# Sheet3.net
KiCad netlist of a schematic drawn in Altium Designer
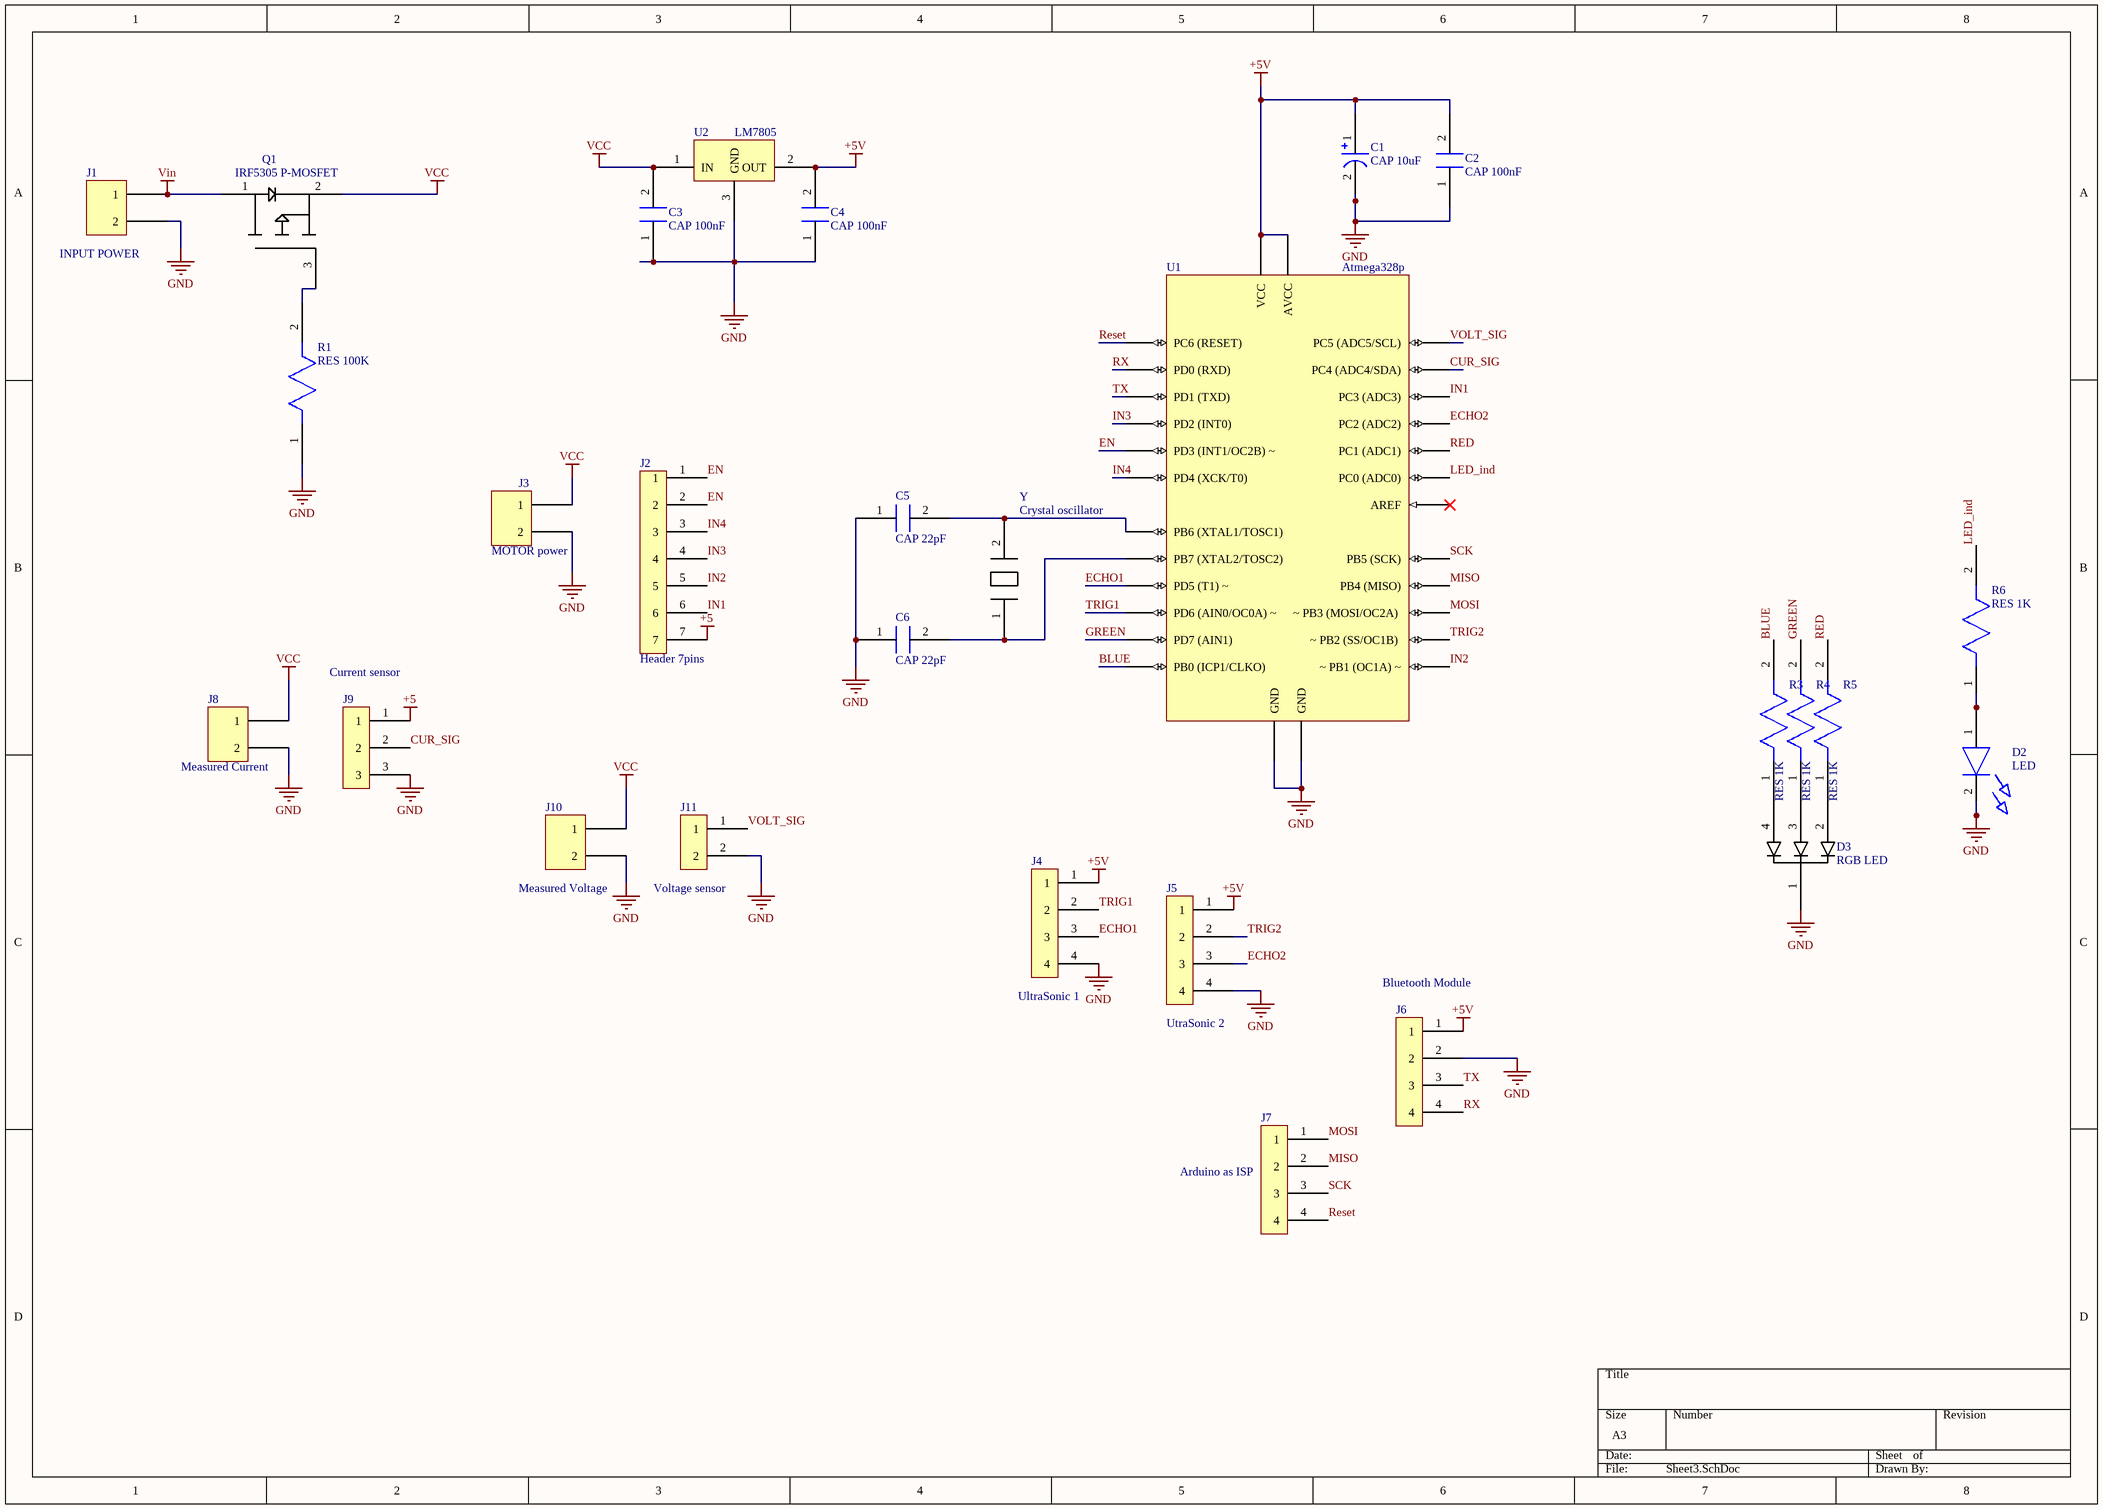
[diagram p0: Sheet3.SchDoc]

(export (version "E")
  (design (tool "Eeschema 10.0.6"))
  (components
    (comp (ref "C1")
      (value "CAP 10uF")
      (footprint "Cap 10uF")
      (libsource (lib "Schlib1") (part "CAP 10uF_1"))
    )
    (comp (ref "C2")
      (value "CAP 100nF")
      (footprint "Cap 100nF")
      (libsource (lib "Schlib1") (part "CAP 100nF"))
    )
    (comp (ref "C3")
      (value "CAP 100nF")
      (footprint "Cap 100nF")
      (libsource (lib "Schlib1") (part "CAP 100nF"))
    )
    (comp (ref "C4")
      (value "CAP 100nF")
      (footprint "Cap 100nF")
      (libsource (lib "Schlib1") (part "CAP 100nF"))
    )
    (comp (ref "C5") (value "CAP 22pF") (footprint "Cap 22pF") (libsource (lib "Schlib1") (part "CAP 22pF")))
    (comp (ref "C6") (value "CAP 22pF") (footprint "Cap 22pF") (libsource (lib "Schlib1") (part "CAP 22pF")))
    (comp (ref "D2") (value "LED") (footprint "LED") (libsource (lib "Schlib1") (part "LED")))
    (comp (ref "D3") (value "RGB LED") (footprint "RGB LED") (libsource (lib "Schlib1") (part "RGB LED")))
    (comp (ref "J1")
      (value "INPUT POWER")
      (footprint "Terminal Block 2pin")
      (libsource (lib "Schlib1") (part "TerminalBlock 2pin"))
    )
    (comp (ref "J2")
      (value "Header 7pins")
      (footprint "Header 7pins")
      (libsource (lib "Schlib1") (part "Header 7pins"))
    )
    (comp (ref "J3")
      (value "MOTOR power")
      (footprint "Terminal Block 2pin")
      (libsource (lib "Schlib1") (part "TerminalBlock 2pin"))
    )
    (comp (ref "J4")
      (value "UltraSonic 1")
      (footprint "Header 4pin")
      (libsource (lib "Schlib1") (part "Headers 4pin"))
    )
    (comp (ref "J5")
      (value "UtraSonic 2")
      (footprint "Header 4pin")
      (libsource (lib "Schlib1") (part "Headers 4pin"))
    )
    (comp (ref "J6")
      (value "Bluetooth Module")
      (footprint "Header 4pin")
      (libsource (lib "Schlib1") (part "Headers 4pin"))
    )
    (comp (ref "J7")
      (value "Arduino as ISP")
      (footprint "Header 4pin")
      (libsource (lib "Schlib1") (part "Headers 4pin"))
    )
    (comp (ref "J8")
      (value "Measured Current")
      (footprint "Terminal Block 2pin")
      (libsource (lib "Schlib1") (part "TerminalBlock 2pin"))
    )
    (comp (ref "J9")
      (value "Current sensor")
      (footprint "Headers 3pins")
      (libsource (lib "Schlib1") (part "Header 3pins"))
    )
    (comp (ref "J10")
      (value "Measured Voltage")
      (footprint "Terminal Block 2pin")
      (libsource (lib "Schlib1") (part "TerminalBlock 2pin"))
    )
    (comp (ref "J11")
      (value "Voltage sensor")
      (footprint "Header 2pins")
      (libsource (lib "Schlib1") (part "Headers 2pins"))
    )
    (comp (ref "Q1")
      (value "IRF5305 P-MOSFET")
      (footprint "IRF5305")
      (libsource (lib "Schlib1") (part "IRF5305 P-MOSFET"))
    )
    (comp (ref "R1") (value "RES 100K") (footprint "Res100K") (libsource (lib "Schlib1") (part "RES 100K")))
    (comp (ref "R3") (value "RES 1K") (footprint "Res 1K") (libsource (lib "Schlib1") (part "RES 1K")))
    (comp (ref "R4") (value "RES 1K") (footprint "Res 1K") (libsource (lib "Schlib1") (part "RES 1K")))
    (comp (ref "R5") (value "RES 1K") (footprint "Res 1K") (libsource (lib "Schlib1") (part "RES 1K")))
    (comp (ref "R6") (value "RES 1K") (footprint "Res 1K") (libsource (lib "Schlib1") (part "RES 1K")))
    (comp (ref "U1")
      (value "Atmega328p")
      (footprint "ATMega 328 P-PU - duplicate")
      (libsource (lib "Schlib1") (part "Atmega328p"))
    )
    (comp (ref "U2") (value "LM7805") (footprint "LM7805") (libsource (lib "Schlib1") (part "LM7805")))
    (comp (ref "Y")
      (value "Crystal oscillator")
      (footprint "Crrystal 16MHZ")
      (libsource (lib "Schlib1") (part "Crystal oscillator"))
    )
  )
  (nets
    (net (code "1") (name "+5") (class "Default")
      (node (ref "J2") (pin "7") (pinfunction "7_7") (pintype "passive"))
      (node (ref "J9") (pin "1") (pinfunction "1_1") (pintype "passive"))
    )
    (net (code "2") (name "+5V") (class "Default")
      (node (ref "C1") (pin "1") (pinfunction "1_1") (pintype "passive"))
      (node (ref "C2") (pin "2") (pinfunction "2_2") (pintype "passive"))
      (node (ref "C4") (pin "2") (pinfunction "2_2") (pintype "passive"))
      (node (ref "J4") (pin "1") (pinfunction "1_1") (pintype "passive"))
      (node (ref "J5") (pin "1") (pinfunction "1_1") (pintype "passive"))
      (node (ref "J6") (pin "1") (pinfunction "1_1") (pintype "passive"))
      (node (ref "U1") (pin "20") (pinfunction "AVCC_20") (pintype "passive"))
      (node (ref "U1") (pin "7") (pinfunction "VCC_7") (pintype "passive"))
      (node (ref "U2") (pin "2") (pinfunction "OUT_2") (pintype "passive"))
    )
    (net (code "4") (name "/BLUE") (class "Default")
      (node (ref "R3") (pin "2") (pinfunction "4_2") (pintype "passive"))
      (node (ref "U1") (pin "14") (pinfunction "PB0_(ICP1/CLKO)_14") (pintype "bidirectional"))
    )
    (net (code "5") (name "/CUR_SIG") (class "Default")
      (node (ref "J9") (pin "2") (pinfunction "2_2") (pintype "passive"))
      (node (ref "U1") (pin "27") (pinfunction "PC4_(ADC4/SDA)_27") (pintype "bidirectional"))
    )
    (net (code "6") (name "/ECHO1") (class "Default")
      (node (ref "J4") (pin "3") (pinfunction "3_3") (pintype "passive"))
      (node (ref "U1") (pin "11") (pinfunction "PD5_(T1)_~_11") (pintype "bidirectional"))
    )
    (net (code "7") (name "/ECHO2") (class "Default")
      (node (ref "J5") (pin "3") (pinfunction "3_3") (pintype "passive"))
      (node (ref "U1") (pin "25") (pinfunction "PC2_(ADC2)_25") (pintype "bidirectional"))
    )
    (net (code "8") (name "/EN") (class "Default")
      (node (ref "J2") (pin "1") (pinfunction "1_1") (pintype "passive"))
      (node (ref "J2") (pin "2") (pinfunction "2_2") (pintype "passive"))
      (node (ref "U1") (pin "5") (pinfunction "PD3_(INT1/OC2B)_~_5") (pintype "bidirectional"))
    )
    (net (code "9") (name "/GREEN") (class "Default")
      (node (ref "R4") (pin "2") (pinfunction "4_2") (pintype "passive"))
      (node (ref "U1") (pin "13") (pinfunction "PD7_(AIN1)_13") (pintype "bidirectional"))
    )
    (net (code "10") (name "/IN1") (class "Default")
      (node (ref "J2") (pin "6") (pinfunction "6_6") (pintype "passive"))
      (node (ref "U1") (pin "26") (pinfunction "PC3_(ADC3)_26") (pintype "bidirectional"))
    )
    (net (code "11") (name "/IN2") (class "Default")
      (node (ref "J2") (pin "5") (pinfunction "5_5") (pintype "passive"))
      (node (ref "U1") (pin "15") (pinfunction "~_PB1_(OC1A)_~_15") (pintype "bidirectional"))
    )
    (net (code "12") (name "/IN3") (class "Default")
      (node (ref "J2") (pin "4") (pinfunction "4_4") (pintype "passive"))
      (node (ref "U1") (pin "4") (pinfunction "PD2_(INT0)_4") (pintype "bidirectional"))
    )
    (net (code "13") (name "/IN4") (class "Default")
      (node (ref "J2") (pin "3") (pinfunction "3_3") (pintype "passive"))
      (node (ref "U1") (pin "6") (pinfunction "PD4_(XCK/T0)_6") (pintype "bidirectional"))
    )
    (net (code "14") (name "/LED_ind") (class "Default")
      (node (ref "R6") (pin "2") (pinfunction "4_2") (pintype "passive"))
      (node (ref "U1") (pin "23") (pinfunction "PC0_(ADC0)_23") (pintype "bidirectional"))
    )
    (net (code "15") (name "/MISO") (class "Default")
      (node (ref "J7") (pin "2") (pinfunction "2_2") (pintype "passive"))
      (node (ref "U1") (pin "18") (pinfunction "PB4_(MISO)_18") (pintype "bidirectional"))
    )
    (net (code "16") (name "/MOSI") (class "Default")
      (node (ref "J7") (pin "1") (pinfunction "1_1") (pintype "passive"))
      (node (ref "U1") (pin "17") (pinfunction "~_PB3_(MOSI/OC2A)_17") (pintype "bidirectional"))
    )
    (net (code "17") (name "/RED") (class "Default")
      (node (ref "R5") (pin "2") (pinfunction "4_2") (pintype "passive"))
      (node (ref "U1") (pin "24") (pinfunction "PC1_(ADC1)_24") (pintype "bidirectional"))
    )
    (net (code "18") (name "/RX") (class "Default")
      (node (ref "J6") (pin "4") (pinfunction "4_4") (pintype "passive"))
      (node (ref "U1") (pin "2") (pinfunction "PD0_(RXD)_2") (pintype "bidirectional"))
    )
    (net (code "19") (name "/Reset") (class "Default")
      (node (ref "J7") (pin "4") (pinfunction "4_4") (pintype "passive"))
      (node (ref "U1") (pin "1") (pinfunction "PC6_(RESET)_1") (pintype "bidirectional"))
    )
    (net (code "20") (name "/SCK") (class "Default")
      (node (ref "J7") (pin "3") (pinfunction "3_3") (pintype "passive"))
      (node (ref "U1") (pin "19") (pinfunction "PB5_(SCK)_19") (pintype "bidirectional"))
    )
    (net (code "21") (name "/TRIG1") (class "Default")
      (node (ref "J4") (pin "2") (pinfunction "2_2") (pintype "passive"))
      (node (ref "U1") (pin "12") (pinfunction "PD6_(AIN0/OC0A)_~_12") (pintype "bidirectional"))
    )
    (net (code "22") (name "/TRIG2") (class "Default")
      (node (ref "J5") (pin "2") (pinfunction "2_2") (pintype "passive"))
      (node (ref "U1") (pin "16") (pinfunction "~_PB2_(SS/OC1B)_16") (pintype "bidirectional"))
    )
    (net (code "23") (name "/TX") (class "Default")
      (node (ref "J6") (pin "3") (pinfunction "3_3") (pintype "passive"))
      (node (ref "U1") (pin "3") (pinfunction "PD1_(TXD)_3") (pintype "bidirectional"))
    )
    (net (code "24") (name "/VOLT_SIG") (class "Default")
      (node (ref "J11") (pin "1") (pinfunction "1_1") (pintype "passive"))
      (node (ref "U1") (pin "28") (pinfunction "PC5_(ADC5/SCL)_28") (pintype "bidirectional"))
    )
    (net (code "25") (name "GND") (class "Default")
      (node (ref "C1") (pin "2") (pinfunction "2_2") (pintype "passive"))
      (node (ref "C2") (pin "1") (pinfunction "1_1") (pintype "passive"))
      (node (ref "C3") (pin "1") (pinfunction "1_1") (pintype "passive"))
      (node (ref "C4") (pin "1") (pinfunction "1_1") (pintype "passive"))
      (node (ref "C5") (pin "1") (pinfunction "1_1") (pintype "passive"))
      (node (ref "C6") (pin "1") (pinfunction "1_1") (pintype "passive"))
      (node (ref "D2") (pin "2") (pinfunction "6_2") (pintype "passive"))
      (node (ref "D3") (pin "1") (pinfunction "(-)_1") (pintype "passive"))
      (node (ref "J1") (pin "2") (pinfunction "2_2") (pintype "passive"))
      (node (ref "J10") (pin "2") (pinfunction "2_2") (pintype "passive"))
      (node (ref "J11") (pin "2") (pinfunction "2_2") (pintype "passive"))
      (node (ref "J3") (pin "2") (pinfunction "2_2") (pintype "passive"))
      (node (ref "J4") (pin "4") (pinfunction "4_4") (pintype "passive"))
      (node (ref "J5") (pin "4") (pinfunction "4_4") (pintype "passive"))
      (node (ref "J6") (pin "2") (pinfunction "2_2") (pintype "passive"))
      (node (ref "J8") (pin "2") (pinfunction "2_2") (pintype "passive"))
      (node (ref "J9") (pin "3") (pinfunction "3_3") (pintype "passive"))
      (node (ref "R1") (pin "1") (pinfunction "3_1") (pintype "passive"))
      (node (ref "U1") (pin "22") (pinfunction "GND_22") (pintype "passive"))
      (node (ref "U1") (pin "8") (pinfunction "GND_8") (pintype "passive"))
      (node (ref "U2") (pin "3") (pinfunction "GND_3") (pintype "power_in"))
    )
    (net (code "26") (name "Net-(D2-7)") (class "Default")
      (node (ref "D2") (pin "1") (pinfunction "7_1") (pintype "passive"))
      (node (ref "R6") (pin "1") (pinfunction "3_1") (pintype "passive"))
    )
    (net (code "27") (name "Net-(D3-B)") (class "Default")
      (node (ref "D3") (pin "4") (pinfunction "B_4") (pintype "passive"))
      (node (ref "R3") (pin "1") (pinfunction "3_1") (pintype "passive"))
    )
    (net (code "28") (name "Net-(D3-G)") (class "Default")
      (node (ref "D3") (pin "3") (pinfunction "G_3") (pintype "passive"))
      (node (ref "R4") (pin "1") (pinfunction "3_1") (pintype "passive"))
    )
    (net (code "29") (name "Net-(D3-R)") (class "Default")
      (node (ref "D3") (pin "2") (pinfunction "R_2") (pintype "passive"))
      (node (ref "R5") (pin "1") (pinfunction "3_1") (pintype "passive"))
    )
    (net (code "30") (name "Net-(Q1-G)") (class "Default")
      (node (ref "Q1") (pin "3") (pinfunction "G_3") (pintype "passive"))
      (node (ref "R1") (pin "2") (pinfunction "4_2") (pintype "passive"))
    )
    (net (code "31") (name "Net-(U1-PB6_(XTAL1{slash}TOSC1))") (class "Default")
      (node (ref "C5") (pin "2") (pinfunction "2_2") (pintype "passive"))
      (node (ref "U1") (pin "9") (pinfunction "PB6_(XTAL1/TOSC1)_9") (pintype "bidirectional"))
      (node (ref "Y") (pin "2") (pinfunction "2_2") (pintype "passive"))
    )
    (net (code "32") (name "Net-(U1-PB7_(XTAL2{slash}TOSC2))") (class "Default")
      (node (ref "C6") (pin "2") (pinfunction "2_2") (pintype "passive"))
      (node (ref "U1") (pin "10") (pinfunction "PB7_(XTAL2/TOSC2)_10") (pintype "bidirectional"))
      (node (ref "Y") (pin "1") (pinfunction "1_1") (pintype "passive"))
    )
    (net (code "33") (name "VCC") (class "Default")
      (node (ref "C3") (pin "2") (pinfunction "2_2") (pintype "passive"))
      (node (ref "J10") (pin "1") (pinfunction "1_1") (pintype "passive"))
      (node (ref "J3") (pin "1") (pinfunction "1_1") (pintype "passive"))
      (node (ref "J8") (pin "1") (pinfunction "1_1") (pintype "passive"))
      (node (ref "Q1") (pin "2") (pinfunction "S_2") (pintype "passive"))
      (node (ref "U2") (pin "1") (pinfunction "IN_1") (pintype "passive"))
    )
    (net (code "34") (name "Vin") (class "Default")
      (node (ref "J1") (pin "1") (pinfunction "1_1") (pintype "passive"))
      (node (ref "Q1") (pin "1") (pinfunction "D_1") (pintype "passive"))
    )
    (net (code "35") (name "unconnected-(U1-AREF-Pad21)") (class "Default")
      (node (ref "U1") (pin "21") (pinfunction "AREF_21") (pintype "input+no_connect"))
    )
  )
)
